# Power_Sheet.net
KiCad netlist of a schematic drawn in Altium Designer
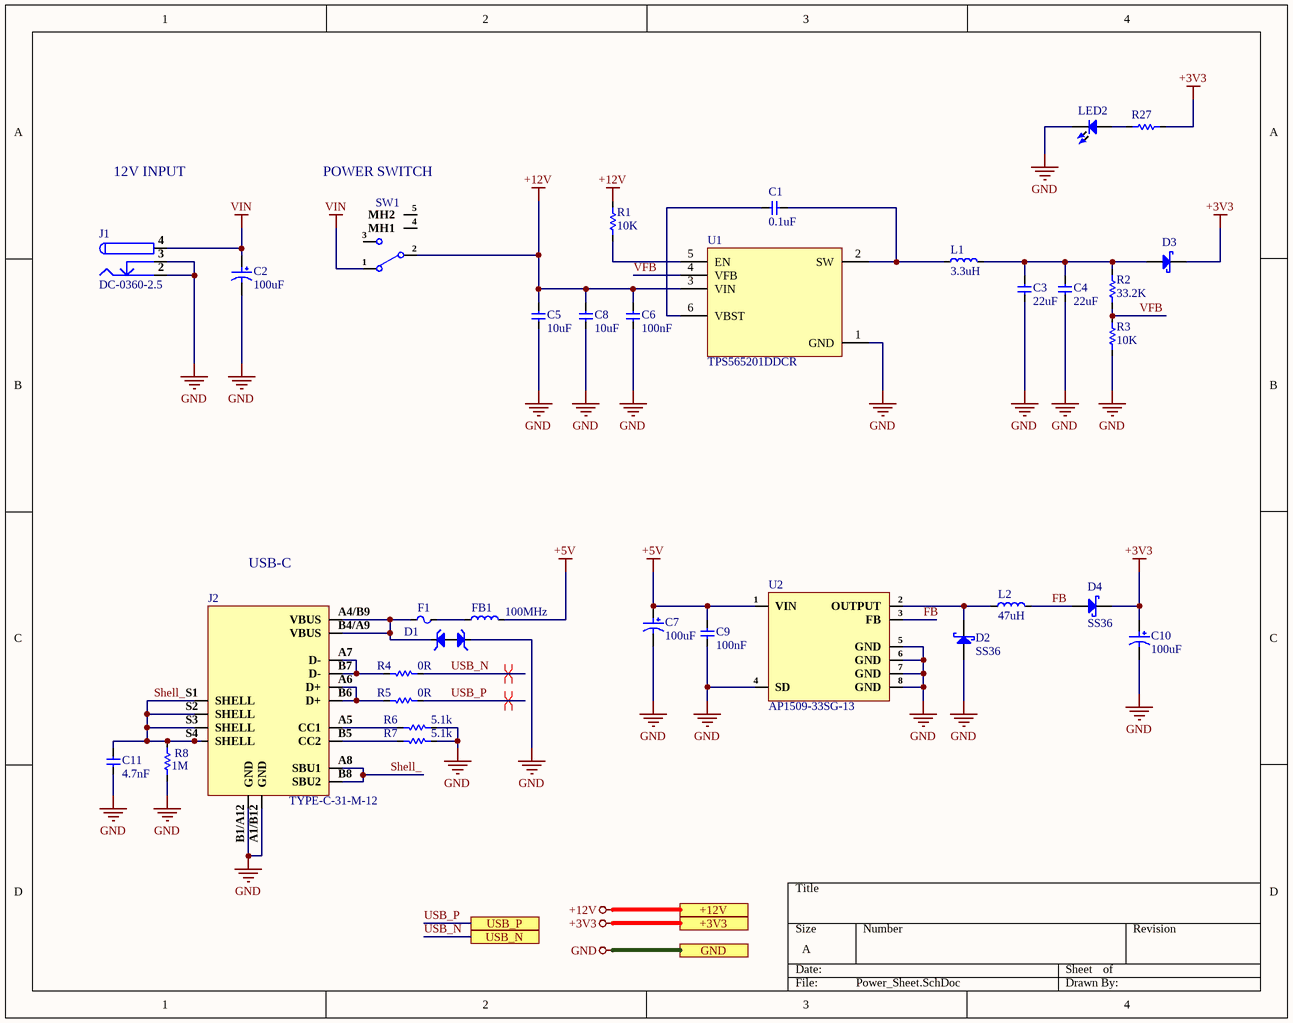
[diagram p0: Power_Sheet.SchDoc]

(export (version "E")
  (design (tool "Eeschema 10.0.6"))
  (components
    (comp (ref "C1")
      (value "0.1uF")
      (footprint "Cap-0603")
      (description "CAP CER 0.1UF 100V X7R 0603")
      (fields
        (field (name "MANUFACTURER") "Yageo")
        (field (name "MANUFACTURER PART NUMBER") "CC0603KRX7R0BB104")
      )
      (libsource (lib "DigitalAzanClock") (part "CC0603KRX7R0BB104"))
    )
    (comp (ref "C2")
      (value "100uF")
      (footprint "RVT1H101M0607")
      (description "100uF 50V ±20% SMD,D6.3xL7.7mm Aluminum Electrolytic Capacitors - SMD ROHS")
      (fields
        (field (name "MANUFACTURER") "ROQANG")
        (field (name "MANUFACTURER PART NUMBER") "RVT1H101M0607")
      )
      (libsource (lib "DigitalAzanClock") (part "RVT1H101M0607"))
    )
    (comp (ref "C3")
      (value "22uF")
      (footprint "Cap-0402")
      (description "CAP CER 22UF 10V X5R 0402")
      (fields
        (field (name "MANUFACTURER") "Murata")
        (field (name "MANUFACTURER PART NUMBER") "GRM158R61A226ME15D")
      )
      (libsource (lib "DigitalAzanClock") (part "GRM158R61A226ME15D"))
    )
    (comp (ref "C4")
      (value "22uF")
      (footprint "Cap-0402")
      (description "CAP CER 22UF 10V X5R 0402")
      (fields
        (field (name "MANUFACTURER") "Murata")
        (field (name "MANUFACTURER PART NUMBER") "GRM158R61A226ME15D")
      )
      (libsource (lib "DigitalAzanClock") (part "GRM158R61A226ME15D"))
    )
    (comp (ref "C5")
      (value "10uF")
      (footprint "Cap-0603")
      (description "10uF 35V X5R 20% Pad SMD 0603")
      (fields
        (field (name "MANUFACTURER") "Murata")
        (field (name "MANUFACTURER PART NUMBER") "GRM188R6YA106MA73D")
      )
      (libsource (lib "DigitalAzanClock") (part "GRM188R6YA106MA73D"))
    )
    (comp (ref "C6")
      (value "100nF")
      (footprint "cap-0402")
      (description "CAP CER 0.1UF 50V X7R 0402")
      (fields
        (field (name "MANUFACTURER") "TDK")
        (field (name "MANUFACTURER PART NUMBER") "C1005X7R1H104KT000F")
      )
      (libsource (lib "DigitalAzanClock") (part "C1005X7R1H104KT000F"))
    )
    (comp (ref "C7")
      (value "100uF")
      (footprint "RVT1H101M0607")
      (description "100uF 50V ±20% SMD,D6.3xL7.7mm Aluminum Electrolytic Capacitors - SMD ROHS")
      (fields
        (field (name "MANUFACTURER") "ROQANG")
        (field (name "MANUFACTURER PART NUMBER") "RVT1H101M0607")
      )
      (libsource (lib "DigitalAzanClock") (part "RVT1H101M0607"))
    )
    (comp (ref "C8")
      (value "10uF")
      (footprint "Cap-0603")
      (description "10uF 35V X5R 20% Pad SMD 0603")
      (fields
        (field (name "MANUFACTURER") "Murata")
        (field (name "MANUFACTURER PART NUMBER") "GRM188R6YA106MA73D")
      )
      (libsource (lib "DigitalAzanClock") (part "GRM188R6YA106MA73D"))
    )
    (comp (ref "C9")
      (value "100nF")
      (footprint "cap-0402")
      (description "CAP CER 0.1UF 50V X7R 0402")
      (fields
        (field (name "MANUFACTURER") "TDK")
        (field (name "MANUFACTURER PART NUMBER") "C1005X7R1H104KT000F")
      )
      (libsource (lib "DigitalAzanClock") (part "C1005X7R1H104KT000F"))
    )
    (comp (ref "C10")
      (value "100uF")
      (footprint "RVT1H101M0607")
      (description "100uF 50V ±20% SMD,D6.3xL7.7mm Aluminum Electrolytic Capacitors - SMD ROHS")
      (fields
        (field (name "MANUFACTURER") "ROQANG")
        (field (name "MANUFACTURER PART NUMBER") "RVT1H101M0607")
      )
      (libsource (lib "DigitalAzanClock") (part "RVT1H101M0607"))
    )
    (comp (ref "C11")
      (value "4.7nF")
      (footprint "Cap-0603")
      (description "CAP CER 4700PF 50V C0G/NPO 0603")
      (fields
        (field (name "MANUFACTURER") "Yageo")
        (field (name "MANUFACTURER PART NUMBER") "CC0603JRNPO9BN472")
      )
      (libsource (lib "DigitalAzanClock") (part "CC0603JRNPO9BN472"))
    )
    (comp (ref "D1")
      (value "~")
      (footprint "DSN0603-2")
      (description "TVS DIODE 5VWM 6.3VC DSN0603-2")
      (fields
        (field (name "MANUFACTURER") "Nexperia")
        (field (name "MANUFACTURER PART NUMBER") "PESD5V0H1BSFYL")
      )
      (libsource (lib "DigitalAzanClock") (part "PESD5V0H1BSFYL"))
    )
    (comp (ref "D2")
      (value "SS36")
      (footprint "SMA")
      (description "Schottky Barrier Diode SK36, DO-214AB, 3A/60V")
      (fields (field (name "MANUFACTURER") "ON Semiconductor / Fairchild") (field (name "VOLTAGE") "60V"))
      (libsource (lib "DigitalAzanClock") (part "SS36"))
    )
    (comp (ref "D3")
      (value "~")
      (footprint "SMB_")
      (description "DIODE SCHOTTKY 5A 40V SMB")
      (fields (field (name "MANUFACTURER") "Comchip") (field (name "MANUFACTURER PART NUMBER") "SS54B-HF"))
      (libsource (lib "DigitalAzanClock") (part "SS54B-HF"))
    )
    (comp (ref "D4")
      (value "SS36")
      (footprint "SMA")
      (description "Schottky Barrier Diode SK36, DO-214AB, 3A/60V")
      (fields (field (name "MANUFACTURER") "ON Semiconductor / Fairchild") (field (name "VOLTAGE") "60V"))
      (libsource (lib "DigitalAzanClock") (part "SS36"))
    )
    (comp (ref "F1")
      (value "~")
      (footprint "Fuse 1206 (3216 Metric)")
      (description "PTC RESET FUSE 6V 3A 1206")
      (fields
        (field (name "MANUFACTURER") "Littelfuse")
        (field (name "MANUFACTURER PART NUMBER") "1206L300SLTHYR")
      )
      (libsource (lib "DigitalAzanClock") (part "1206L300SLTHYR"))
    )
    (comp (ref "FB1")
      (value "100MHz")
      (footprint "IND-1206")
      (description "FERRITE BEAD 120 OHM 1206 1LN")
      (fields
        (field (name "MANUFACTURER") "Murata")
        (field (name "MANUFACTURER PART NUMBER") "BLM31PG121SN1L")
      )
      (libsource (lib "DigitalAzanClock") (part "BLM31PG121SN1L"))
    )
    (comp (ref "J1")
      (value "DC-0360-2.5")
      (footprint "DC-0360-2.5")
      (description "DC Power Receptacle 260℃ Brass -20℃~+70℃ 2.5mm 6mm 2.5A 24V Plugin AC/DC Power Connectors ROHS")
      (fields (field (name "MANUFACTURER") "XKB Connectivity") (field (name "LCSC PART NUMBER") "C319122"))
      (libsource (lib "DigitalAzanClock") (part "DC-0360-2.5"))
    )
    (comp (ref "J2")
      (value "TYPE-C-31-M-12")
      (footprint "TYPE-C-31-M-12_")
      (description "250mA 1 16 Female Type-C SMD USB Connectors ROHS")
      (fields
        (field (name "MANUFACTURER") "Korean Hroparts Elec")
        (field (name "LCSC PART NUMBER") "C165948")
      )
      (libsource (lib "DigitalAzanClock") (part "TYPE-C-31-M-12"))
    )
    (comp (ref "L1")
      (value "3.3uH")
      (footprint "FXL0530-3R3-M")
      (description "5.5A 3.3uH Molding Choke ±20% 6A SMD,5.2x5.4mm Power Inductors ROHS")
      (fields
        (field (name "MANUFACTURER") "cjiang (Changjiang Microelectronics Tech)")
        (field (name "MANUDACTURER PART NUMBER") "FXL0530-3R3-M")
      )
      (libsource (lib "DigitalAzanClock") (part "FXL0530-3R3-M"))
    )
    (comp (ref "L2")
      (value "47uH")
      (footprint "SMMS0650-470M")
      (description "2A 47uH Molding Choke ±20% 2.8A SMD,6.6x7.1mm Power Inductors ROHS")
      (fields
        (field (name "MANUFACTURER") "SXN(Shun Xiang Nuo Elec)")
        (field (name "MANUFACTURER PART NUMBER") "SMMS0650-470M")
      )
      (libsource (lib "DigitalAzanClock") (part "SMMS0650-470M"))
    )
    (comp (ref "LED2")
      (value "~")
      (footprint "LED-0603")
      (description "blue 0603 Light Emitting Diodes (LED) ROHS")
      (fields
        (field (name "MANUFACTURER") "Foshan NationStar Optoelectronics")
        (field (name "MANUFACTURER PART NUMBER") "NCD0603B3")
      )
      (libsource (lib "DigitalAzanClock") (part "NCD0603B3"))
    )
    (comp (ref "R1")
      (value "10K")
      (footprint "Res-0603")
      (description "RES SMD 10K OHM 0.1% 1/10W 0603")
      (fields
        (field (name "MANUFACTURER") "Yageo")
        (field (name "MANUFACTURER PART NUMBER") "RT0603BRD0710KL")
      )
      (libsource (lib "DigitalAzanClock") (part "RT0603BRD0710KL"))
    )
    (comp (ref "R2")
      (value "33.2K")
      (footprint "Res-0603")
      (description "RES 33.2K OHM 1% 1/10W 0603")
      (fields
        (field (name "MANUFACTURER") "Yageo")
        (field (name "MANUFACTURER PART NUMBER") "RC0603FR-0733K2L")
      )
      (libsource (lib "DigitalAzanClock") (part "RC0603FR-0733K2L"))
    )
    (comp (ref "R3")
      (value "10K")
      (footprint "Res-0603")
      (description "RES SMD 10K OHM 0.1% 1/10W 0603")
      (fields
        (field (name "MANUFACTURER") "Yageo")
        (field (name "MANUFACTURER PART NUMBER") "RT0603BRD0710KL")
      )
      (libsource (lib "DigitalAzanClock") (part "RT0603BRD0710KL"))
    )
    (comp (ref "R4")
      (value "0R")
      (footprint "Res-0402")
      (description "RES 0 OHM JUMPER 1/16W 0402")
      (fields
        (field (name "MANUFACTURER") "Yageo")
        (field (name "MANUFACTURER PART NUMBER") "RC0402FR-070RL")
      )
      (libsource (lib "DigitalAzanClock") (part "RC0402FR-070RL"))
    )
    (comp (ref "R5")
      (value "0R")
      (footprint "Res-0402")
      (description "RES 0 OHM JUMPER 1/16W 0402")
      (fields
        (field (name "MANUFACTURER") "Yageo")
        (field (name "MANUFACTURER PART NUMBER") "RC0402FR-070RL")
      )
      (libsource (lib "DigitalAzanClock") (part "RC0402FR-070RL"))
    )
    (comp (ref "R6")
      (value "5.1k")
      (footprint "Res-0201")
      (description "RES 5.1K OHM 1% 1/20W 0201")
      (fields
        (field (name "MANUFACTURER") "Yageo")
        (field (name "MANUFACTURER PART NUMBER") "RC0201FR-075K1L")
      )
      (libsource (lib "DigitalAzanClock") (part "RC0201FR-075K1L"))
    )
    (comp (ref "R7")
      (value "5.1k")
      (footprint "Res-0201")
      (description "RES 5.1K OHM 1% 1/20W 0201")
      (fields
        (field (name "MANUFACTURER") "Yageo")
        (field (name "MANUFACTURER PART NUMBER") "RC0201FR-075K1L")
      )
      (libsource (lib "DigitalAzanClock") (part "RC0201FR-075K1L"))
    )
    (comp (ref "R8")
      (value "1M")
      (footprint "Res-0402")
      (description "RES SMD 1M OHM 5% 1/16W 0402")
      (fields
        (field (name "MANUFACTURER") "Yageo")
        (field (name "MANUFACTURER PART NUMBER") "AF0402JR-071ML")
      )
      (libsource (lib "DigitalAzanClock") (part "AF0402JR-071ML"))
    )
    (comp (ref "R27")
      (value "~")
      (footprint "Res-0402")
      (description "RES 200 OHM 1% 1/16W 0402")
      (fields
        (field (name "MANUFACTURER") "Yageo")
        (field (name "MANUFACTURER PART NUMBER") "RC0402FR-07200RL")
      )
      (libsource (lib "DigitalAzanClock") (part "RC0402FR-07200RL"))
    )
    (comp (ref "SW1")
      (value "~")
      (footprint "SS-12D11L5")
      (fields
        (field (name "MANUFACTURER") "XKB Connectivity")
        (field (name "MANUFACTURER PART NUMBER") "SS-12D11L5")
        (field (name "LCSC PART NUMBER") "C319010")
      )
      (libsource (lib "DigitalAzanClock") (part "SS-12D11L5"))
    )
    (comp (ref "U1")
      (value "TPS565201DDCR")
      (footprint "TPS565201DDCR")
      (description "4.5V to 17V, 5A, Synchronous Step-Down Voltage Regulator in SOT23 6-SOT-23-THIN -40 to 125")
      (fields (field (name "MANUFACTURER") "Texas Instruments") (field (name "LCSC PART NUMBER") "C327676"))
      (libsource (lib "DigitalAzanClock") (part "TPS565201DDCR"))
    )
    (comp (ref "U2")
      (value "AP1509-33SG-13")
      (footprint "SOP-8L")
      (description "IC REG BUCK 3.3V 2A 8SOP")
      (fields (field (name "MANUFACTURER") "Diodes") (field (name "LCSC PART NUMBER") "C151823"))
      (libsource (lib "DigitalAzanClock") (part "AP1509-33SG-13"))
    )
  )
  (nets
    (net (code "1") (name "+3V3") (class "Default")
      (node (ref "C10") (pin "1") (pintype "passive"))
      (node (ref "D3") (pin "2") (pinfunction "K_2") (pintype "passive"))
      (node (ref "D4") (pin "1") (pinfunction "K_1") (pintype "passive"))
      (node (ref "R27") (pin "2") (pinfunction "2_2") (pintype "passive"))
    )
    (net (code "2") (name "+5V") (class "Default")
      (node (ref "C7") (pin "1") (pintype "passive"))
      (node (ref "C9") (pin "2") (pinfunction "2_2") (pintype "passive"))
      (node (ref "FB1") (pin "2") (pinfunction "2_2") (pintype "passive"))
      (node (ref "U2") (pin "1") (pinfunction "VIN_1") (pintype "passive"))
    )
    (net (code "3") (name "+12V") (class "Default")
      (node (ref "C5") (pin "2") (pinfunction "2_2") (pintype "passive"))
      (node (ref "C6") (pin "2") (pinfunction "2_2") (pintype "passive"))
      (node (ref "C8") (pin "2") (pinfunction "2_2") (pintype "passive"))
      (node (ref "R1") (pin "2") (pinfunction "2_2") (pintype "passive"))
      (node (ref "SW1") (pin "2") (pinfunction "2_2") (pintype "passive"))
      (node (ref "U1") (pin "3") (pinfunction "VIN_3") (pintype "power_in"))
    )
    (net (code "4") (name "/FB") (class "Default")
      (node (ref "D4") (pin "2") (pinfunction "A_2") (pintype "passive"))
      (node (ref "L2") (pin "2") (pinfunction "2_2") (pintype "passive"))
      (node (ref "U2") (pin "3") (pinfunction "FB_3") (pintype "passive"))
    )
    (net (code "5") (name "/Shell_") (class "Default")
      (node (ref "C11") (pin "2") (pinfunction "2_2") (pintype "passive"))
      (node (ref "J2") (pin "A8") (pinfunction "SBU1_A8") (pintype "passive"))
      (node (ref "J2") (pin "B8") (pinfunction "SBU2_B8") (pintype "passive"))
      (node (ref "J2") (pin "S1") (pinfunction "SHELL_S1") (pintype "passive"))
      (node (ref "J2") (pin "S2") (pinfunction "SHELL_S2") (pintype "passive"))
      (node (ref "J2") (pin "S3") (pinfunction "SHELL_S3") (pintype "passive"))
      (node (ref "J2") (pin "S4") (pinfunction "SHELL_S4") (pintype "passive"))
      (node (ref "R8") (pin "2") (pinfunction "2_2") (pintype "passive"))
    )
    (net (code "6") (name "/USB_N") (class "Default")
      (node (ref "R4") (pin "2") (pinfunction "2_2") (pintype "passive"))
    )
    (net (code "7") (name "/USB_P") (class "Default")
      (node (ref "R5") (pin "2") (pinfunction "2_2") (pintype "passive"))
    )
    (net (code "8") (name "/VFB") (class "Default")
      (node (ref "R2") (pin "1") (pinfunction "1_1") (pintype "passive"))
      (node (ref "R3") (pin "2") (pinfunction "2_2") (pintype "passive"))
      (node (ref "U1") (pin "4") (pinfunction "VFB_4") (pintype "open_emitter"))
    )
    (net (code "9") (name "GND") (class "Default")
      (node (ref "C10") (pin "2") (pintype "passive"))
      (node (ref "C11") (pin "1") (pinfunction "1_1") (pintype "passive"))
      (node (ref "C2") (pin "2") (pintype "passive"))
      (node (ref "C3") (pin "1") (pinfunction "1_1") (pintype "passive"))
      (node (ref "C4") (pin "1") (pinfunction "1_1") (pintype "passive"))
      (node (ref "C5") (pin "1") (pinfunction "1_1") (pintype "passive"))
      (node (ref "C6") (pin "1") (pinfunction "1_1") (pintype "passive"))
      (node (ref "C7") (pin "2") (pintype "passive"))
      (node (ref "C8") (pin "1") (pinfunction "1_1") (pintype "passive"))
      (node (ref "C9") (pin "1") (pinfunction "1_1") (pintype "passive"))
      (node (ref "D1") (pin "2") (pinfunction "2_2") (pintype "passive"))
      (node (ref "D2") (pin "2") (pinfunction "A_2") (pintype "passive"))
      (node (ref "J1") (pin "2") (pinfunction "2_2") (pintype "power_in"))
      (node (ref "J1") (pin "3") (pinfunction "3_3") (pintype "power_in"))
      (node (ref "J2") (pin "A1/B12") (pinfunction "GND_A1/B12") (pintype "power_in"))
      (node (ref "J2") (pin "B1/A12") (pinfunction "GND_B1/A12") (pintype "power_in"))
      (node (ref "LED2") (pin "2") (pinfunction "2_2") (pintype "passive"))
      (node (ref "R3") (pin "1") (pinfunction "1_1") (pintype "passive"))
      (node (ref "R6") (pin "1") (pinfunction "1_1") (pintype "passive"))
      (node (ref "R7") (pin "1") (pinfunction "1_1") (pintype "passive"))
      (node (ref "R8") (pin "1") (pinfunction "1_1") (pintype "passive"))
      (node (ref "U1") (pin "1") (pinfunction "GND_1") (pintype "power_in"))
      (node (ref "U2") (pin "4") (pinfunction "SD_4") (pintype "passive"))
      (node (ref "U2") (pin "5") (pinfunction "GND_5") (pintype "passive"))
      (node (ref "U2") (pin "6") (pinfunction "GND_6") (pintype "passive"))
      (node (ref "U2") (pin "7") (pinfunction "GND_7") (pintype "passive"))
      (node (ref "U2") (pin "8") (pinfunction "GND_8") (pintype "passive"))
    )
    (net (code "10") (name "Net-(D1-Pad1)") (class "Default")
      (node (ref "D1") (pin "1") (pinfunction "1_1") (pintype "passive"))
      (node (ref "F1") (pin "1") (pinfunction "1_1") (pintype "passive"))
      (node (ref "J2") (pin "A4/B9") (pinfunction "VBUS_A4/B9") (pintype "power_in"))
      (node (ref "J2") (pin "B4/A9") (pinfunction "VBUS_B4/A9") (pintype "power_in"))
    )
    (net (code "11") (name "Net-(D2-K)") (class "Default")
      (node (ref "D2") (pin "1") (pinfunction "K_1") (pintype "passive"))
      (node (ref "L2") (pin "1") (pinfunction "1_1") (pintype "passive"))
      (node (ref "U2") (pin "2") (pinfunction "OUTPUT_2") (pintype "passive"))
    )
    (net (code "12") (name "Net-(D3-A)") (class "Default")
      (node (ref "C3") (pin "2") (pinfunction "2_2") (pintype "passive"))
      (node (ref "C4") (pin "2") (pinfunction "2_2") (pintype "passive"))
      (node (ref "D3") (pin "1") (pinfunction "A_1") (pintype "passive"))
      (node (ref "L1") (pin "2") (pinfunction "2_2") (pintype "passive"))
      (node (ref "R2") (pin "2") (pinfunction "2_2") (pintype "passive"))
    )
    (net (code "13") (name "Net-(F1-Pad2)") (class "Default")
      (node (ref "F1") (pin "2") (pinfunction "2_2") (pintype "passive"))
      (node (ref "FB1") (pin "1") (pinfunction "1_1") (pintype "passive"))
    )
    (net (code "14") (name "Net-(J2-CC1)") (class "Default")
      (node (ref "J2") (pin "A5") (pinfunction "CC1_A5") (pintype "passive"))
      (node (ref "R6") (pin "2") (pinfunction "2_2") (pintype "passive"))
    )
    (net (code "15") (name "Net-(J2-CC2)") (class "Default")
      (node (ref "J2") (pin "B5") (pinfunction "CC2_B5") (pintype "passive"))
      (node (ref "R7") (pin "2") (pinfunction "2_2") (pintype "passive"))
    )
    (net (code "16") (name "Net-(J2-D+-PadA6)") (class "Default")
      (node (ref "J2") (pin "A6") (pinfunction "D+_A6") (pintype "passive"))
      (node (ref "J2") (pin "B6") (pinfunction "D+_B6") (pintype "passive"))
      (node (ref "R5") (pin "1") (pinfunction "1_1") (pintype "passive"))
    )
    (net (code "17") (name "Net-(J2-D--PadA7)") (class "Default")
      (node (ref "J2") (pin "A7") (pinfunction "D-_A7") (pintype "passive"))
      (node (ref "J2") (pin "B7") (pinfunction "D-_B7") (pintype "passive"))
      (node (ref "R4") (pin "1") (pinfunction "1_1") (pintype "passive"))
    )
    (net (code "18") (name "Net-(LED2-Pad1)") (class "Default")
      (node (ref "LED2") (pin "1") (pinfunction "1_1") (pintype "passive"))
      (node (ref "R27") (pin "1") (pinfunction "1_1") (pintype "passive"))
    )
    (net (code "19") (name "Net-(U1-EN)") (class "Default")
      (node (ref "R1") (pin "1") (pinfunction "1_1") (pintype "passive"))
      (node (ref "U1") (pin "5") (pinfunction "EN_5") (pintype "open_emitter"))
    )
    (net (code "20") (name "Net-(U1-SW)") (class "Default")
      (node (ref "C1") (pin "2") (pinfunction "2_2") (pintype "passive"))
      (node (ref "L1") (pin "1") (pinfunction "1_1") (pintype "passive"))
      (node (ref "U1") (pin "2") (pinfunction "SW_2") (pintype "power_in"))
    )
    (net (code "21") (name "Net-(U1-VBST)") (class "Default")
      (node (ref "C1") (pin "1") (pinfunction "1_1") (pintype "passive"))
      (node (ref "U1") (pin "6") (pinfunction "VBST_6") (pintype "open_emitter"))
    )
    (net (code "22") (name "VIN") (class "Default")
      (node (ref "C2") (pin "1") (pintype "passive"))
      (node (ref "J1") (pin "4") (pinfunction "4_4") (pintype "power_in"))
      (node (ref "SW1") (pin "1") (pinfunction "1_1") (pintype "passive"))
    )
    (net (code "23") (name "unconnected-(SW1-MH1-Pad4)") (class "Default")
      (node (ref "SW1") (pin "4") (pinfunction "MH1_4") (pintype "passive"))
    )
    (net (code "24") (name "unconnected-(SW1-MH2-Pad5)") (class "Default")
      (node (ref "SW1") (pin "5") (pinfunction "MH2_5") (pintype "passive"))
    )
    (net (code "25") (name "unconnected-(SW1-Pad3)") (class "Default")
      (node (ref "SW1") (pin "3") (pinfunction "3_3") (pintype "passive"))
    )
  )
)
